# Ampli.net
KiCad netlist of a schematic drawn in Altium Designer
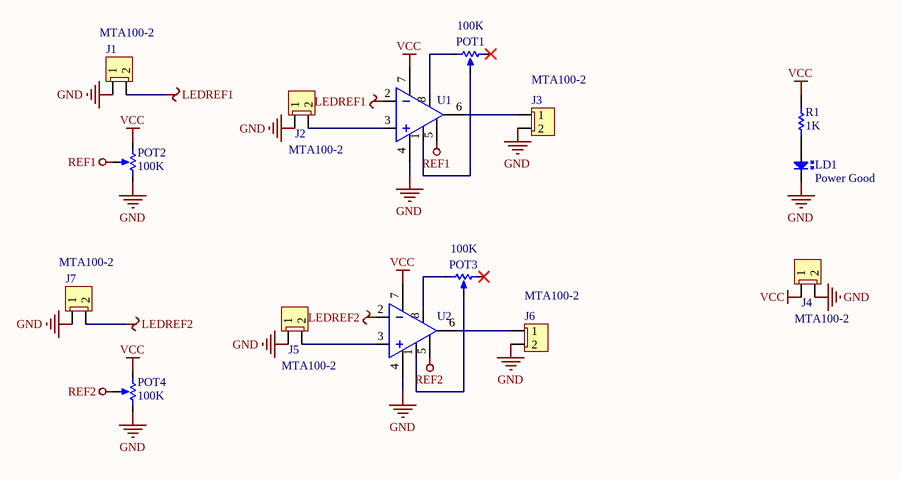
[diagram p0: Ampli.SchDoc]

(export (version "E")
  (design (tool "Eeschema 10.0.6"))
  (components
    (comp (ref "J1")
      (value "Input")
      (footprint "MTA100-2")
      (description "MTA Male 0 Degres")
      (fields (field (name "CONNECTOR TYPE") "MTA100-2"))
      (libsource (lib "") (part "MTA100-2_1"))
    )
    (comp (ref "J2")
      (value "Input")
      (footprint "MTA100-2")
      (description "MTA Male 0 Degres")
      (fields (field (name "CONNECTOR TYPE") "MTA100-2"))
      (libsource (lib "") (part "MTA100-2_1"))
    )
    (comp (ref "J3")
      (value "Input")
      (footprint "MTA100-2")
      (description "MTA Male 0 Degres")
      (fields (field (name "CONNECTOR TYPE") "MTA100-2"))
      (libsource (lib "Lib Sch") (part "MTA100-2"))
    )
    (comp (ref "J4")
      (value "Input")
      (footprint "MTA100-2")
      (description "MTA Male 0 Degres")
      (fields (field (name "CONNECTOR TYPE") "MTA100-2"))
      (libsource (lib "") (part "MTA100-2_1"))
    )
    (comp (ref "J5")
      (value "Input")
      (footprint "MTA100-2")
      (description "MTA Male 0 Degres")
      (fields (field (name "CONNECTOR TYPE") "MTA100-2"))
      (libsource (lib "") (part "MTA100-2_1"))
    )
    (comp (ref "J6")
      (value "Input")
      (footprint "MTA100-2")
      (description "MTA Male 0 Degres")
      (fields (field (name "CONNECTOR TYPE") "MTA100-2"))
      (libsource (lib "Lib Sch") (part "MTA100-2"))
    )
    (comp (ref "J7")
      (value "Input")
      (footprint "MTA100-2")
      (description "MTA Male 0 Degres")
      (fields (field (name "CONNECTOR TYPE") "MTA100-2"))
      (libsource (lib "") (part "MTA100-2_1"))
    )
    (comp (ref "LD1")
      (value "Power Good")
      (footprint "LED 3mm Vertical")
      (description "Through Hole")
      (fields (field (name "PUBLISHER") "Altium Limited"))
      (libsource (lib "Lib Sch") (part "LED 3mm Vertical"))
    )
    (comp (ref "POT1")
      (value "100K")
      (footprint "VR1")
      (fields (field (name "Comment") "?????"))
      (libsource (lib "Lib Sch") (part "Res Pot 10T Vertical"))
    )
    (comp (ref "POT2")
      (value "100K")
      (footprint "VR1")
      (fields (field (name "Comment") "?????"))
      (libsource (lib "Lib Sch") (part "Res Pot 10T Vertical"))
    )
    (comp (ref "POT3")
      (value "100K")
      (footprint "VR1")
      (fields (field (name "Comment") "?????"))
      (libsource (lib "Lib Sch") (part "Res Pot 10T Vertical"))
    )
    (comp (ref "POT4")
      (value "100K")
      (footprint "VR1")
      (fields (field (name "Comment") "?????"))
      (libsource (lib "Lib Sch") (part "Res Pot 10T Vertical"))
    )
    (comp (ref "R1")
      (value "1K")
      (footprint "Axial 0.4\" Step")
      (description "Resistor")
      (fields (field (name "Comment") "Res 1/4W") (field (name "PUBLISHER") "Altium Limited"))
      (libsource (lib "Lib Sch") (part "Res 1/4W"))
    )
    (comp (ref "U1")
      (value "OpAmp Single")
      (footprint "DIP8")
      (libsource (lib "Lib Sch") (part "OpAmp Single"))
    )
    (comp (ref "U2")
      (value "OpAmp Single")
      (footprint "DIP8")
      (libsource (lib "Lib Sch") (part "OpAmp Single"))
    )
  )
  (nets
    (net (code "1") (name "GND") (class "Default")
      (node (ref "J1") (pin "1") (pinfunction "1_1") (pintype "passive"))
      (node (ref "J2") (pin "1") (pinfunction "1_1") (pintype "passive"))
      (node (ref "J3") (pin "2") (pinfunction "2_2") (pintype "passive"))
      (node (ref "J4") (pin "2") (pinfunction "2_2") (pintype "passive"))
      (node (ref "J5") (pin "1") (pinfunction "1_1") (pintype "passive"))
      (node (ref "J6") (pin "2") (pinfunction "2_2") (pintype "passive"))
      (node (ref "J7") (pin "1") (pinfunction "1_1") (pintype "passive"))
      (node (ref "LD1") (pin "2") (pinfunction "K_2") (pintype "passive"))
      (node (ref "POT2") (pin "3") (pinfunction "Bot_3") (pintype "passive"))
      (node (ref "POT4") (pin "3") (pinfunction "Bot_3") (pintype "passive"))
      (node (ref "U1") (pin "4") (pinfunction "-Vcc_4") (pintype "passive"))
      (node (ref "U2") (pin "4") (pinfunction "-Vcc_4") (pintype "passive"))
    )
    (net (code "2") (name "LEDREF1") (class "Default")
      (node (ref "J1") (pin "2") (pinfunction "2_2") (pintype "passive"))
      (node (ref "U1") (pin "2") (pinfunction "-_2") (pintype "passive"))
    )
    (net (code "3") (name "LEDREF2") (class "Default")
      (node (ref "J7") (pin "2") (pinfunction "2_2") (pintype "passive"))
      (node (ref "U2") (pin "2") (pinfunction "-_2") (pintype "passive"))
    )
    (net (code "4") (name "Net-(LD1-A)") (class "Default")
      (node (ref "LD1") (pin "1") (pinfunction "A_1") (pintype "passive"))
      (node (ref "R1") (pin "2") (pinfunction "2_2") (pintype "passive"))
    )
    (net (code "5") (name "Net-(POT1-Tap)") (class "Default")
      (node (ref "POT1") (pin "2") (pinfunction "Tap_2") (pintype "passive"))
      (node (ref "U1") (pin "1") (pinfunction "B_1") (pintype "passive"))
    )
    (net (code "6") (name "Net-(POT1-Top)") (class "Default")
      (node (ref "POT1") (pin "1") (pinfunction "Top_1") (pintype "passive"))
      (node (ref "U1") (pin "8") (pinfunction "NC_8") (pintype "passive"))
    )
    (net (code "7") (name "Net-(POT3-Tap)") (class "Default")
      (node (ref "POT3") (pin "2") (pinfunction "Tap_2") (pintype "passive"))
      (node (ref "U2") (pin "1") (pinfunction "B_1") (pintype "passive"))
    )
    (net (code "8") (name "Net-(POT3-Top)") (class "Default")
      (node (ref "POT3") (pin "1") (pinfunction "Top_1") (pintype "passive"))
      (node (ref "U2") (pin "8") (pinfunction "NC_8") (pintype "passive"))
    )
    (net (code "9") (name "Net-(U1-+)") (class "Default")
      (node (ref "J2") (pin "2") (pinfunction "2_2") (pintype "passive"))
      (node (ref "U1") (pin "3") (pinfunction "+_3") (pintype "passive"))
    )
    (net (code "10") (name "Net-(U1-Out)") (class "Default")
      (node (ref "J3") (pin "1") (pinfunction "1_1") (pintype "passive"))
      (node (ref "U1") (pin "6") (pinfunction "Out_6") (pintype "passive"))
    )
    (net (code "11") (name "Net-(U2-+)") (class "Default")
      (node (ref "J5") (pin "2") (pinfunction "2_2") (pintype "passive"))
      (node (ref "U2") (pin "3") (pinfunction "+_3") (pintype "passive"))
    )
    (net (code "12") (name "Net-(U2-Out)") (class "Default")
      (node (ref "J6") (pin "1") (pinfunction "1_1") (pintype "passive"))
      (node (ref "U2") (pin "6") (pinfunction "Out_6") (pintype "passive"))
    )
    (net (code "13") (name "REF1") (class "Default")
      (node (ref "POT2") (pin "2") (pinfunction "Tap_2") (pintype "passive"))
      (node (ref "U1") (pin "5") (pinfunction "B_5") (pintype "passive"))
    )
    (net (code "14") (name "REF2") (class "Default")
      (node (ref "POT4") (pin "2") (pinfunction "Tap_2") (pintype "passive"))
      (node (ref "U2") (pin "5") (pinfunction "B_5") (pintype "passive"))
    )
    (net (code "15") (name "VCC") (class "Default")
      (node (ref "J4") (pin "1") (pinfunction "1_1") (pintype "passive"))
      (node (ref "POT2") (pin "1") (pinfunction "Top_1") (pintype "passive"))
      (node (ref "POT4") (pin "1") (pinfunction "Top_1") (pintype "passive"))
      (node (ref "R1") (pin "1") (pinfunction "1_1") (pintype "passive"))
      (node (ref "U1") (pin "7") (pinfunction "+Vcc_7") (pintype "passive"))
      (node (ref "U2") (pin "7") (pinfunction "+Vcc_7") (pintype "passive"))
    )
    (net (code "16") (name "unconnected-(POT1-Bot-Pad3)") (class "Default")
      (node (ref "POT1") (pin "3") (pinfunction "Bot_3") (pintype "passive+no_connect"))
    )
    (net (code "17") (name "unconnected-(POT3-Bot-Pad3)") (class "Default")
      (node (ref "POT3") (pin "3") (pinfunction "Bot_3") (pintype "passive+no_connect"))
    )
  )
)
